# CAT6_snake.net
KiCad netlist of a schematic drawn in EAGLE
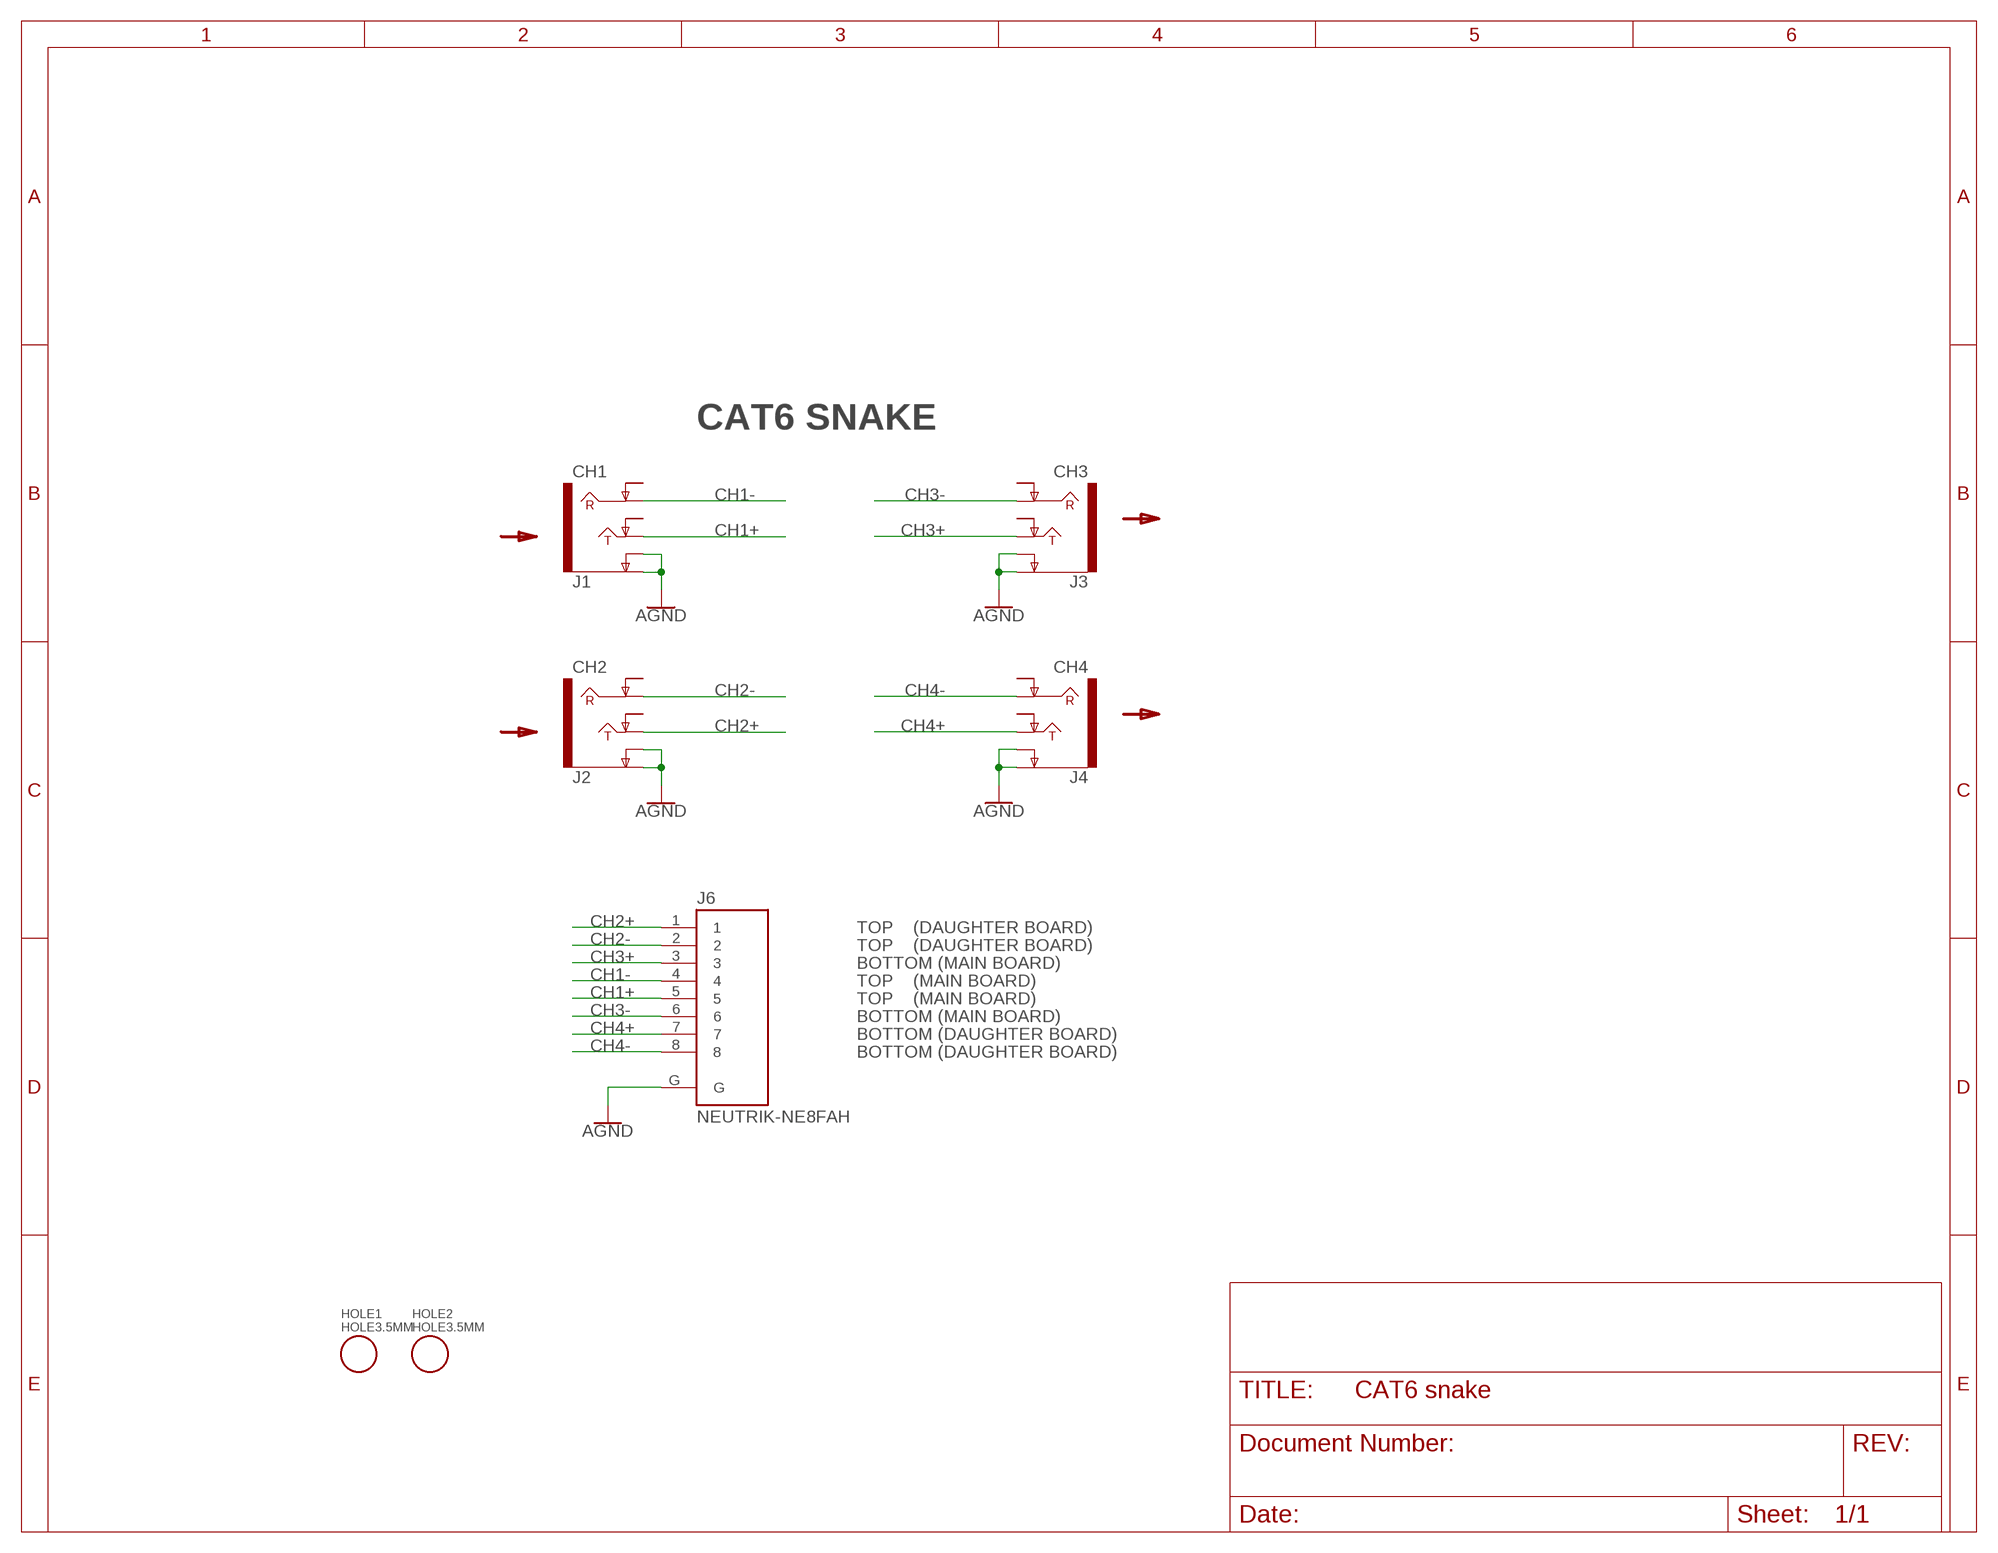
[diagram p0: schematic, sheet 1]

(export (version "E")
  (design (tool "Eeschema 10.0.6"))
  (components
    (comp (ref "HOLE1")
      (value "HOLE3.5MM")
      (footprint "eagle-import:HOLE-3.5MM")
      (libsource (lib "eagle-import") (part "HOLE3.5MM"))
    )
    (comp (ref "HOLE2")
      (value "HOLE3.5MM")
      (footprint "eagle-import:HOLE-3.5MM")
      (libsource (lib "eagle-import") (part "HOLE3.5MM"))
    )
    (comp (ref "J1")
      (value "CH1")
      (footprint "eagle-import:NEUTRIK-NRJ6HF")
      (libsource (lib "eagle-import") (part "AUDIO_JACK_TRS_0.25{dblquote}_PTH_RA-NRJ6HM"))
    )
    (comp (ref "J2")
      (value "CH2")
      (footprint "eagle-import:NEUTRIK-NRJ6HF")
      (libsource (lib "eagle-import") (part "AUDIO_JACK_TRS_0.25{dblquote}_PTH_RA-NRJ6HM"))
    )
    (comp (ref "J3")
      (value "CH3")
      (footprint "eagle-import:NEUTRIK-NRJ6HF")
      (libsource (lib "eagle-import") (part "AUDIO_JACK_TRS_0.25{dblquote}_PTH_RA-NRJ6HM"))
    )
    (comp (ref "J4")
      (value "CH4")
      (footprint "eagle-import:NEUTRIK-NRJ6HF")
      (libsource (lib "eagle-import") (part "AUDIO_JACK_TRS_0.25{dblquote}_PTH_RA-NRJ6HM"))
    )
    (comp (ref "J6")
      (value "NEUTRIK-NE8FAH")
      (footprint "eagle-import:NEUTRIK_NE8FAH")
      (fields (field (name "MF") "Neutrik") (field (name "MP") "NE8FAH"))
      (libsource (lib "eagle-import") (part "NEUTRIK-NE8FAH"))
    )
  )
  (nets
    (net (code "1") (name "/CH1+") (class "Default")
      (node (ref "J1") (pin "T") (pinfunction "TIP_T") (pintype "bidirectional"))
      (node (ref "J6") (pin "5") (pinfunction "5_5") (pintype "passive"))
    )
    (net (code "2") (name "/CH1-") (class "Default")
      (node (ref "J1") (pin "R") (pinfunction "RING_R") (pintype "bidirectional"))
      (node (ref "J6") (pin "4") (pinfunction "4_4") (pintype "passive"))
    )
    (net (code "3") (name "/CH2+") (class "Default")
      (node (ref "J2") (pin "T") (pinfunction "TIP_T") (pintype "bidirectional"))
      (node (ref "J6") (pin "1") (pinfunction "1_1") (pintype "passive"))
    )
    (net (code "4") (name "/CH2-") (class "Default")
      (node (ref "J2") (pin "R") (pinfunction "RING_R") (pintype "bidirectional"))
      (node (ref "J6") (pin "2") (pinfunction "2_2") (pintype "passive"))
    )
    (net (code "5") (name "/CH3+") (class "Default")
      (node (ref "J3") (pin "T") (pinfunction "TIP_T") (pintype "bidirectional"))
      (node (ref "J6") (pin "3") (pinfunction "3_3") (pintype "passive"))
    )
    (net (code "6") (name "/CH3-") (class "Default")
      (node (ref "J3") (pin "R") (pinfunction "RING_R") (pintype "bidirectional"))
      (node (ref "J6") (pin "6") (pinfunction "6_6") (pintype "passive"))
    )
    (net (code "7") (name "/CH4+") (class "Default")
      (node (ref "J4") (pin "T") (pinfunction "TIP_T") (pintype "bidirectional"))
      (node (ref "J6") (pin "7") (pinfunction "7_7") (pintype "passive"))
    )
    (net (code "8") (name "/CH4-") (class "Default")
      (node (ref "J4") (pin "R") (pinfunction "RING_R") (pintype "bidirectional"))
      (node (ref "J6") (pin "8") (pinfunction "8_8") (pintype "passive"))
    )
    (net (code "9") (name "AGND") (class "Default")
      (node (ref "J1") (pin "S") (pinfunction "EARTH_S") (pintype "bidirectional"))
      (node (ref "J1") (pin "SN") (pinfunction "EARTH-NORM_SN") (pintype "bidirectional"))
      (node (ref "J2") (pin "S") (pinfunction "EARTH_S") (pintype "bidirectional"))
      (node (ref "J2") (pin "SN") (pinfunction "EARTH-NORM_SN") (pintype "bidirectional"))
      (node (ref "J3") (pin "S") (pinfunction "EARTH_S") (pintype "bidirectional"))
      (node (ref "J3") (pin "SN") (pinfunction "EARTH-NORM_SN") (pintype "bidirectional"))
      (node (ref "J4") (pin "S") (pinfunction "EARTH_S") (pintype "bidirectional"))
      (node (ref "J4") (pin "SN") (pinfunction "EARTH-NORM_SN") (pintype "bidirectional"))
      (node (ref "J6") (pin "G") (pinfunction "G_G") (pintype "power_in"))
    )
    (net (code "10") (name "unconnected-(J1-RING-NORM-PadRN)") (class "Default")
      (node (ref "J1") (pin "RN") (pinfunction "RING-NORM_RN") (pintype "bidirectional"))
    )
    (net (code "11") (name "unconnected-(J1-TIP-NORM-PadTN)") (class "Default")
      (node (ref "J1") (pin "TN") (pinfunction "TIP-NORM_TN") (pintype "bidirectional"))
    )
    (net (code "12") (name "unconnected-(J2-RING-NORM-PadRN)") (class "Default")
      (node (ref "J2") (pin "RN") (pinfunction "RING-NORM_RN") (pintype "bidirectional"))
    )
    (net (code "13") (name "unconnected-(J2-TIP-NORM-PadTN)") (class "Default")
      (node (ref "J2") (pin "TN") (pinfunction "TIP-NORM_TN") (pintype "bidirectional"))
    )
    (net (code "14") (name "unconnected-(J3-RING-NORM-PadRN)") (class "Default")
      (node (ref "J3") (pin "RN") (pinfunction "RING-NORM_RN") (pintype "bidirectional"))
    )
    (net (code "15") (name "unconnected-(J3-TIP-NORM-PadTN)") (class "Default")
      (node (ref "J3") (pin "TN") (pinfunction "TIP-NORM_TN") (pintype "bidirectional"))
    )
    (net (code "16") (name "unconnected-(J4-RING-NORM-PadRN)") (class "Default")
      (node (ref "J4") (pin "RN") (pinfunction "RING-NORM_RN") (pintype "bidirectional"))
    )
    (net (code "17") (name "unconnected-(J4-TIP-NORM-PadTN)") (class "Default")
      (node (ref "J4") (pin "TN") (pinfunction "TIP-NORM_TN") (pintype "bidirectional"))
    )
  )
)
